# P1_1.net
KiCad netlist of a schematic drawn in EasyEDA Pro
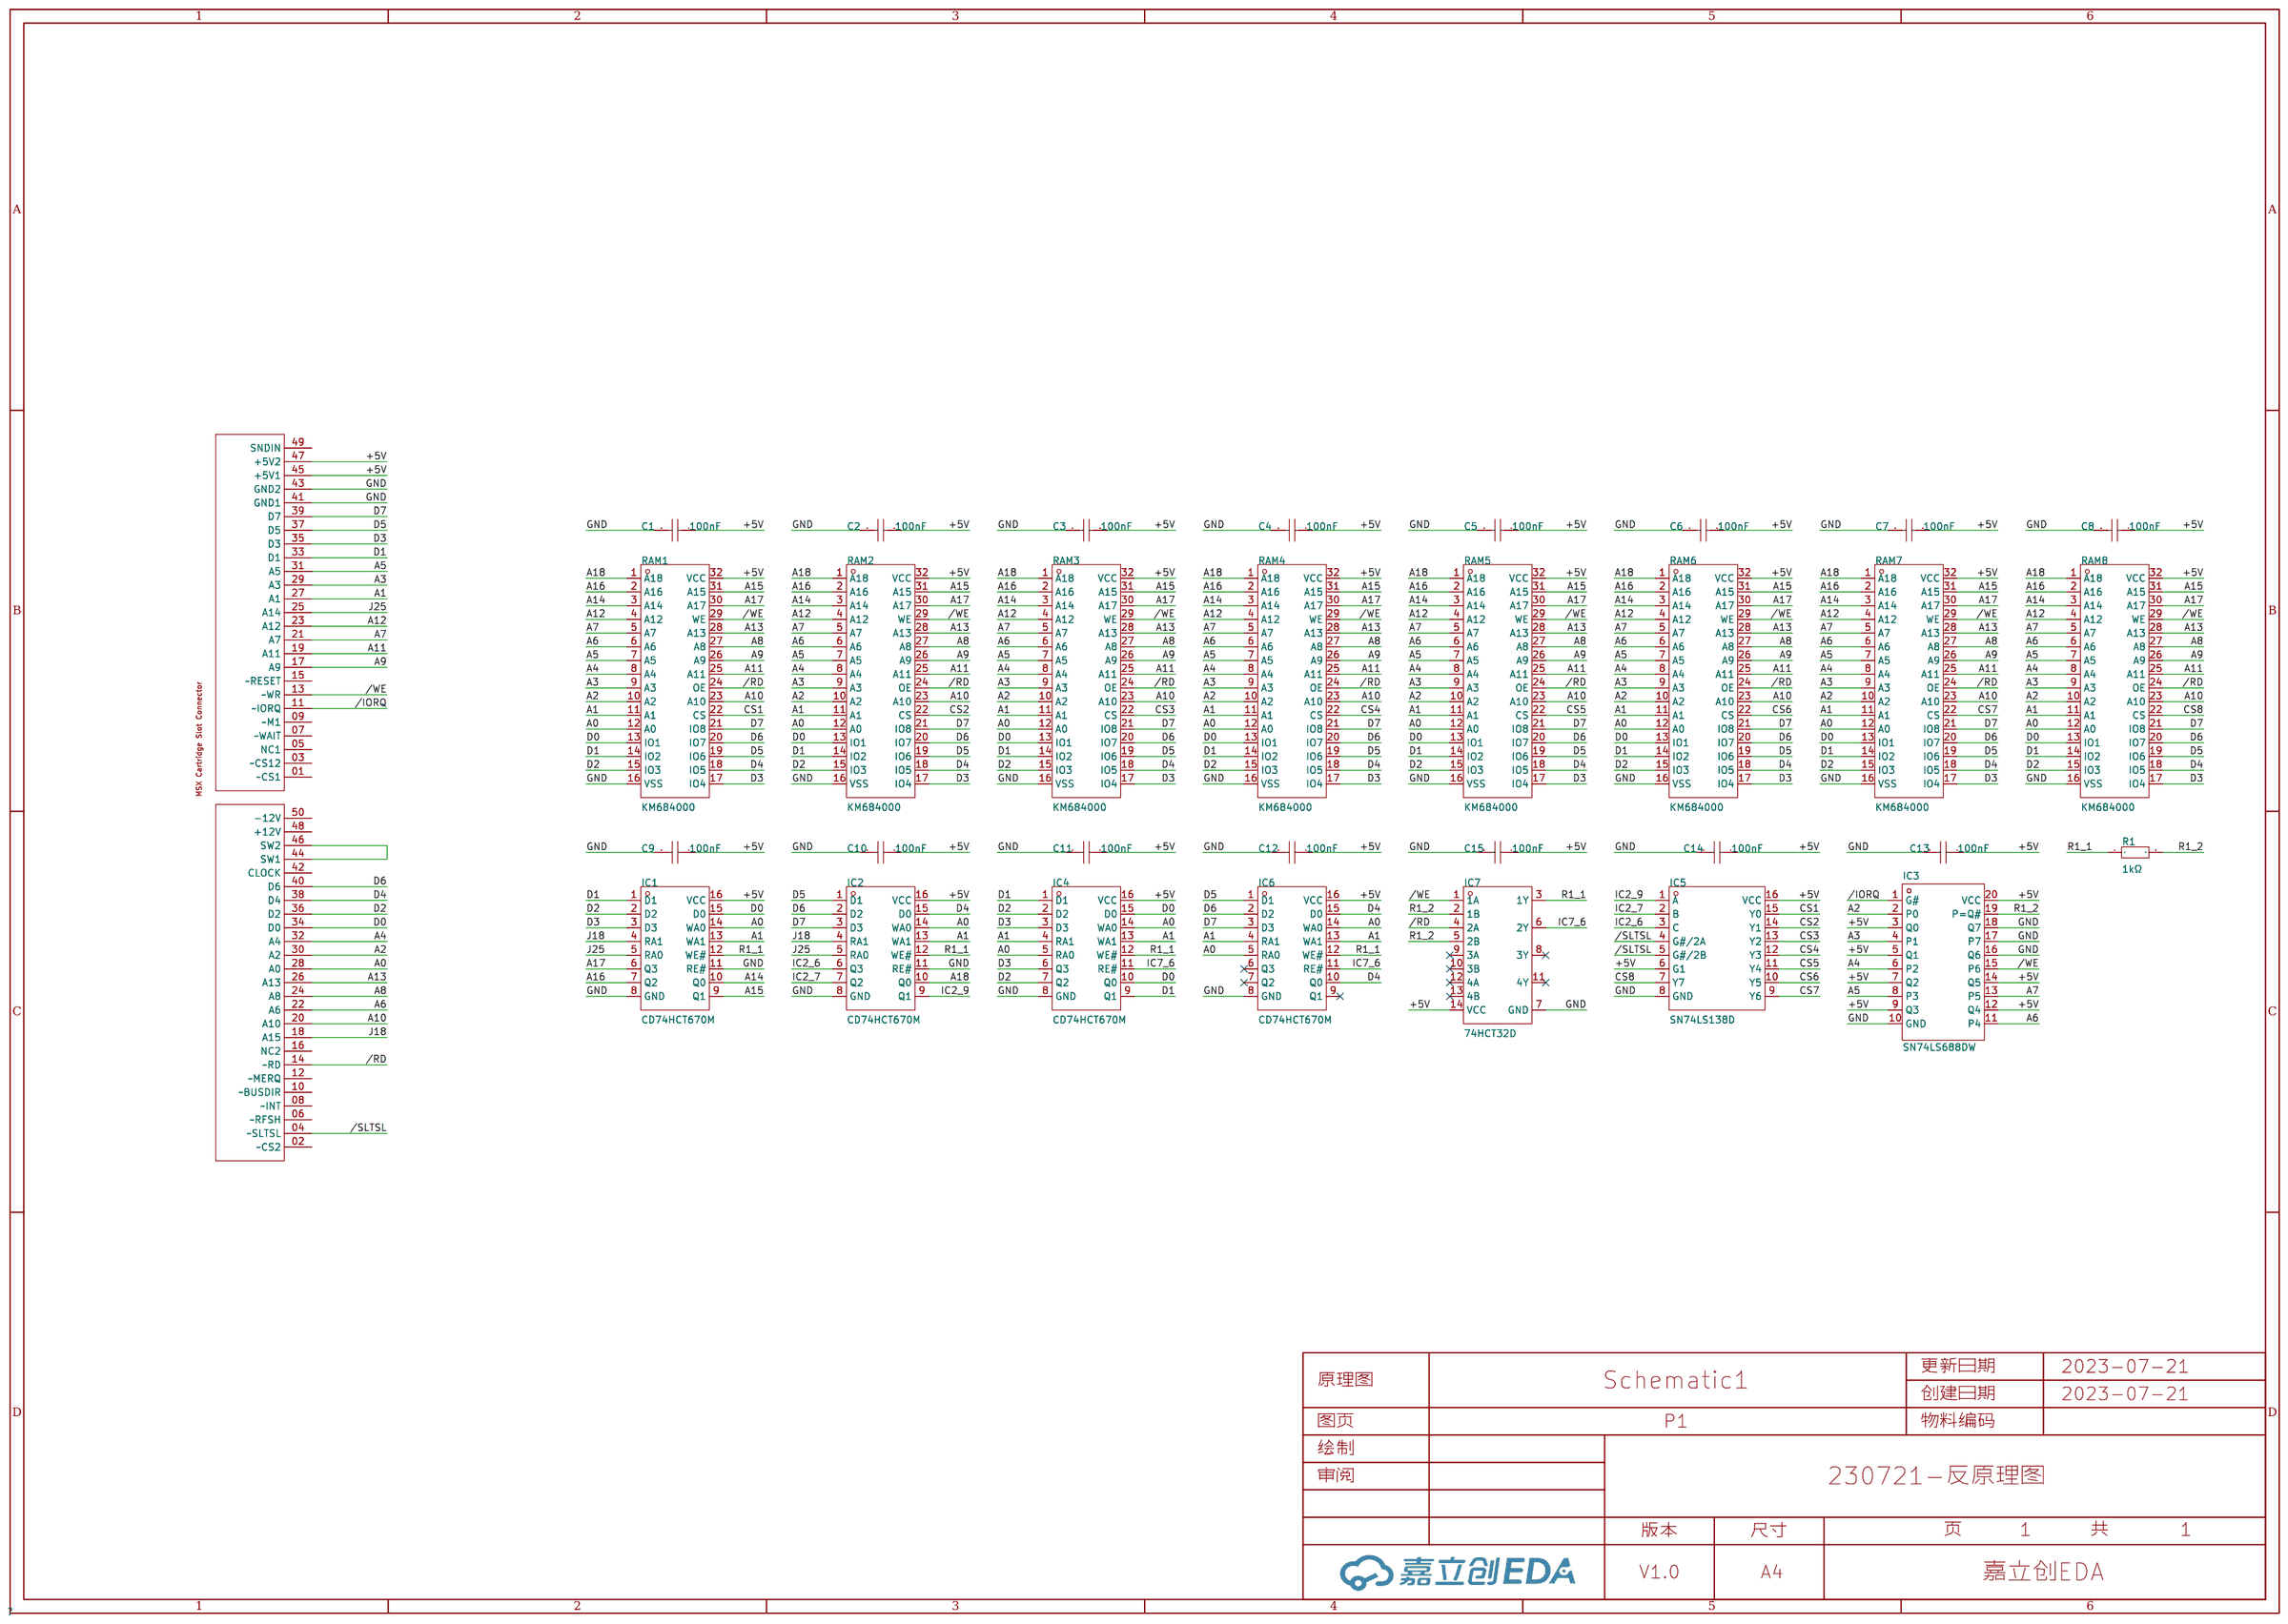
[diagram p0: schematic sheet]

(export (version "E")
  (design (tool "Eeschema 10.0.6"))
  (components
    (comp (ref "C1")
      (value "100nF")
      (footprint "easyedapro:C0805")
      (description "容值:100nF;精度:±10%;额定电压:50V;材质(温度系数):X7R;")
      (fields
        (field (name "Manufacturer Part") "CC0805KRX7R9BB104")
        (field (name "Manufacturer") "YAGEO(国巨)")
      )
      (libsource (lib "easyedapro") (part "CC0805KRX7R9BB104"))
    )
    (comp (ref "C2")
      (value "100nF")
      (footprint "easyedapro:C0805")
      (description "容值:100nF;精度:±10%;额定电压:50V;材质(温度系数):X7R;")
      (fields
        (field (name "Manufacturer Part") "CC0805KRX7R9BB104")
        (field (name "Manufacturer") "YAGEO(国巨)")
      )
      (libsource (lib "easyedapro") (part "CC0805KRX7R9BB104"))
    )
    (comp (ref "C3")
      (value "100nF")
      (footprint "easyedapro:C0805")
      (description "容值:100nF;精度:±10%;额定电压:50V;材质(温度系数):X7R;")
      (fields
        (field (name "Manufacturer Part") "CC0805KRX7R9BB104")
        (field (name "Manufacturer") "YAGEO(国巨)")
      )
      (libsource (lib "easyedapro") (part "CC0805KRX7R9BB104"))
    )
    (comp (ref "C4")
      (value "100nF")
      (footprint "easyedapro:C0805")
      (description "容值:100nF;精度:±10%;额定电压:50V;材质(温度系数):X7R;")
      (fields
        (field (name "Manufacturer Part") "CC0805KRX7R9BB104")
        (field (name "Manufacturer") "YAGEO(国巨)")
      )
      (libsource (lib "easyedapro") (part "CC0805KRX7R9BB104"))
    )
    (comp (ref "C5")
      (value "100nF")
      (footprint "easyedapro:C0805")
      (description "容值:100nF;精度:±10%;额定电压:50V;材质(温度系数):X7R;")
      (fields
        (field (name "Manufacturer Part") "CC0805KRX7R9BB104")
        (field (name "Manufacturer") "YAGEO(国巨)")
      )
      (libsource (lib "easyedapro") (part "CC0805KRX7R9BB104"))
    )
    (comp (ref "C6")
      (value "100nF")
      (footprint "easyedapro:C0805")
      (description "容值:100nF;精度:±10%;额定电压:50V;材质(温度系数):X7R;")
      (fields
        (field (name "Manufacturer Part") "CC0805KRX7R9BB104")
        (field (name "Manufacturer") "YAGEO(国巨)")
      )
      (libsource (lib "easyedapro") (part "CC0805KRX7R9BB104"))
    )
    (comp (ref "C7")
      (value "100nF")
      (footprint "easyedapro:C0805")
      (description "容值:100nF;精度:±10%;额定电压:50V;材质(温度系数):X7R;")
      (fields
        (field (name "Manufacturer Part") "CC0805KRX7R9BB104")
        (field (name "Manufacturer") "YAGEO(国巨)")
      )
      (libsource (lib "easyedapro") (part "CC0805KRX7R9BB104"))
    )
    (comp (ref "C8")
      (value "100nF")
      (footprint "easyedapro:C0805")
      (description "容值:100nF;精度:±10%;额定电压:50V;材质(温度系数):X7R;")
      (fields
        (field (name "Manufacturer Part") "CC0805KRX7R9BB104")
        (field (name "Manufacturer") "YAGEO(国巨)")
      )
      (libsource (lib "easyedapro") (part "CC0805KRX7R9BB104"))
    )
    (comp (ref "C9")
      (value "100nF")
      (footprint "easyedapro:C0805")
      (description "容值:100nF;精度:±10%;额定电压:50V;材质(温度系数):X7R;")
      (fields
        (field (name "Manufacturer Part") "CC0805KRX7R9BB104")
        (field (name "Manufacturer") "YAGEO(国巨)")
      )
      (libsource (lib "easyedapro") (part "CC0805KRX7R9BB104"))
    )
    (comp (ref "C10")
      (value "100nF")
      (footprint "easyedapro:C0805")
      (description "容值:100nF;精度:±10%;额定电压:50V;材质(温度系数):X7R;")
      (fields
        (field (name "Manufacturer Part") "CC0805KRX7R9BB104")
        (field (name "Manufacturer") "YAGEO(国巨)")
      )
      (libsource (lib "easyedapro") (part "CC0805KRX7R9BB104"))
    )
    (comp (ref "C11")
      (value "100nF")
      (footprint "easyedapro:C0805")
      (description "容值:100nF;精度:±10%;额定电压:50V;材质(温度系数):X7R;")
      (fields
        (field (name "Manufacturer Part") "CC0805KRX7R9BB104")
        (field (name "Manufacturer") "YAGEO(国巨)")
      )
      (libsource (lib "easyedapro") (part "CC0805KRX7R9BB104"))
    )
    (comp (ref "C12")
      (value "100nF")
      (footprint "easyedapro:C0805")
      (description "容值:100nF;精度:±10%;额定电压:50V;材质(温度系数):X7R;")
      (fields
        (field (name "Manufacturer Part") "CC0805KRX7R9BB104")
        (field (name "Manufacturer") "YAGEO(国巨)")
      )
      (libsource (lib "easyedapro") (part "CC0805KRX7R9BB104"))
    )
    (comp (ref "C13")
      (value "100nF")
      (footprint "easyedapro:C0805")
      (description "容值:100nF;精度:±10%;额定电压:50V;材质(温度系数):X7R;")
      (fields
        (field (name "Manufacturer Part") "CC0805KRX7R9BB104")
        (field (name "Manufacturer") "YAGEO(国巨)")
      )
      (libsource (lib "easyedapro") (part "CC0805KRX7R9BB104"))
    )
    (comp (ref "C14")
      (value "100nF")
      (footprint "easyedapro:C0805")
      (description "容值:100nF;精度:±10%;额定电压:50V;材质(温度系数):X7R;")
      (fields
        (field (name "Manufacturer Part") "CC0805KRX7R9BB104")
        (field (name "Manufacturer") "YAGEO(国巨)")
      )
      (libsource (lib "easyedapro") (part "CC0805KRX7R9BB104"))
    )
    (comp (ref "C15")
      (value "100nF")
      (footprint "easyedapro:C0805")
      (description "容值:100nF;精度:±10%;额定电压:50V;材质(温度系数):X7R;")
      (fields
        (field (name "Manufacturer Part") "CC0805KRX7R9BB104")
        (field (name "Manufacturer") "YAGEO(国巨)")
      )
      (libsource (lib "easyedapro") (part "CC0805KRX7R9BB104"))
    )
    (comp (ref "IC1")
      (value "CD74HCT670M")
      (footprint "easyedapro:SOIC-16_L9.9-W3.9-P1.27-LS6.0-BL")
      (description "高速 CMOS 逻辑 4 x 4 寄存器文件 16-SOIC -55 to 125")
      (fields (field (name "Manufacturer") "TI(德州仪器)"))
      (libsource (lib "easyedapro") (part "CD74HCT670M"))
    )
    (comp (ref "IC2")
      (value "CD74HCT670M")
      (footprint "easyedapro:SOIC-16_L9.9-W3.9-P1.27-LS6.0-BL")
      (description "高速 CMOS 逻辑 4 x 4 寄存器文件 16-SOIC -55 to 125")
      (fields (field (name "Manufacturer") "TI(德州仪器)"))
      (libsource (lib "easyedapro") (part "CD74HCT670M"))
    )
    (comp (ref "IC3")
      (value "SN74LS688DW")
      (footprint "easyedapro:SOIC-20_L12.8-W7.5-P1.27-LS10.3-BL")
      (description "具有使能端的 8 位等值/幅度比较器 (P=Q) 20-SOIC 0 to 70")
      (fields (field (name "Manufacturer") "TI(德州仪器)"))
      (libsource (lib "easyedapro") (part "SN74LS688DW"))
    )
    (comp (ref "IC4")
      (value "CD74HCT670M")
      (footprint "easyedapro:SOIC-16_L9.9-W3.9-P1.27-LS6.0-BL")
      (description "高速 CMOS 逻辑 4 x 4 寄存器文件 16-SOIC -55 to 125")
      (fields (field (name "Manufacturer") "TI(德州仪器)"))
      (libsource (lib "easyedapro") (part "CD74HCT670M"))
    )
    (comp (ref "IC5")
      (value "SN74LS138D")
      (footprint "easyedapro:SOIC-16_L9.9-W3.9-P1.27-LS6.0-BL")
      (description "类型:解码器/多路解器;低电平输出电流(IOL):8mA;高电平输出电流(IOH):400uA;供电电源:单电源;供电电压:4.75V~5.25V;工作温度:0°C~+70°C;")
      (fields (field (name "Manufacturer") "TI(德州仪器)"))
      (libsource (lib "easyedapro") (part "SN74LS138D"))
    )
    (comp (ref "IC6")
      (value "CD74HCT670M")
      (footprint "easyedapro:SOIC-16_L9.9-W3.9-P1.27-LS6.0-BL")
      (description "高速 CMOS 逻辑 4 x 4 寄存器文件 16-SOIC -55 to 125")
      (fields (field (name "Manufacturer") "TI(德州仪器)"))
      (libsource (lib "easyedapro") (part "CD74HCT670M"))
    )
    (comp (ref "IC7")
      (value "74HCT32D")
      (footprint "easyedapro:SOIC-14_L8.6-W3.9-P1.27-LS6.0-BL")
      (description "逻辑类型:或门;通道数:4;电源电压:4.5V~5.5V;静态电流(最大值):1uA;最大传播延迟:18ns@5.5V,50pF;")
      (fields (field (name "Manufacturer") "TOSHIBA(东芝)"))
      (libsource (lib "easyedapro") (part "74HCT32D"))
    )
    (comp (ref "J2")
      (value "MSX_SLOT_CON")
      (libsource (lib "easyedapro") (part "msx2proto-eagle-import_MSX_SLOT_CON"))
    )
    (comp (ref "R1")
      (value "1kΩ")
      (footprint "easyedapro:R0805")
      (description "电阻类型:厚膜电阻;阻值:1kΩ;精度:±1%;功率:125mW;")
      (fields
        (field (name "Manufacturer Part") "0805W8F1001T5E")
        (field (name "Manufacturer") "UNI-ROYAL(厚声)")
      )
      (libsource (lib "easyedapro") (part "0805W8F1001T5E"))
    )
    (comp (ref "RAM1")
      (value "KM684000")
      (footprint "easyedapro:SOP-32_L20.9-W11.4-P1.27-LS14.12-BL")
      (description "存储器类型:-;存储器容量:-;存储器接口类型:-;工作电压:-;")
      (libsource (lib "easyedapro") (part "KM684000"))
    )
    (comp (ref "RAM2")
      (value "KM684000")
      (footprint "easyedapro:SOP-32_L20.9-W11.4-P1.27-LS14.12-BL")
      (description "存储器类型:-;存储器容量:-;存储器接口类型:-;工作电压:-;")
      (libsource (lib "easyedapro") (part "KM684000"))
    )
    (comp (ref "RAM3")
      (value "KM684000")
      (footprint "easyedapro:SOP-32_L20.9-W11.4-P1.27-LS14.12-BL")
      (description "存储器类型:-;存储器容量:-;存储器接口类型:-;工作电压:-;")
      (libsource (lib "easyedapro") (part "KM684000"))
    )
    (comp (ref "RAM4")
      (value "KM684000")
      (footprint "easyedapro:SOP-32_L20.9-W11.4-P1.27-LS14.12-BL")
      (description "存储器类型:-;存储器容量:-;存储器接口类型:-;工作电压:-;")
      (libsource (lib "easyedapro") (part "KM684000"))
    )
    (comp (ref "RAM5")
      (value "KM684000")
      (footprint "easyedapro:SOP-32_L20.9-W11.4-P1.27-LS14.12-BL")
      (description "存储器类型:-;存储器容量:-;存储器接口类型:-;工作电压:-;")
      (libsource (lib "easyedapro") (part "KM684000"))
    )
    (comp (ref "RAM6")
      (value "KM684000")
      (footprint "easyedapro:SOP-32_L20.9-W11.4-P1.27-LS14.12-BL")
      (description "存储器类型:-;存储器容量:-;存储器接口类型:-;工作电压:-;")
      (libsource (lib "easyedapro") (part "KM684000"))
    )
    (comp (ref "RAM7")
      (value "KM684000")
      (footprint "easyedapro:SOP-32_L20.9-W11.4-P1.27-LS14.12-BL")
      (description "存储器类型:-;存储器容量:-;存储器接口类型:-;工作电压:-;")
      (libsource (lib "easyedapro") (part "KM684000"))
    )
    (comp (ref "RAM8")
      (value "KM684000")
      (footprint "easyedapro:SOP-32_L20.9-W11.4-P1.27-LS14.12-BL")
      (description "存储器类型:-;存储器容量:-;存储器接口类型:-;工作电压:-;")
      (libsource (lib "easyedapro") (part "KM684000"))
    )
  )
  (nets
    (net (code "1") (name "/+5V") (class "Default")
      (node (ref "C1") (pin "1") (pinfunction "1_1") (pintype "input"))
      (node (ref "C10") (pin "1") (pinfunction "1_1") (pintype "input"))
      (node (ref "C11") (pin "1") (pinfunction "1_1") (pintype "input"))
      (node (ref "C12") (pin "1") (pinfunction "1_1") (pintype "input"))
      (node (ref "C13") (pin "1") (pinfunction "1_1") (pintype "input"))
      (node (ref "C14") (pin "1") (pinfunction "1_1") (pintype "input"))
      (node (ref "C15") (pin "1") (pinfunction "1_1") (pintype "input"))
      (node (ref "C2") (pin "1") (pinfunction "1_1") (pintype "input"))
      (node (ref "C3") (pin "1") (pinfunction "1_1") (pintype "input"))
      (node (ref "C4") (pin "1") (pinfunction "1_1") (pintype "input"))
      (node (ref "C5") (pin "1") (pinfunction "1_1") (pintype "input"))
      (node (ref "C6") (pin "1") (pinfunction "1_1") (pintype "input"))
      (node (ref "C7") (pin "1") (pinfunction "1_1") (pintype "input"))
      (node (ref "C8") (pin "1") (pinfunction "1_1") (pintype "input"))
      (node (ref "C9") (pin "1") (pinfunction "1_1") (pintype "input"))
      (node (ref "IC1") (pin "16") (pinfunction "VCC_16") (pintype "input"))
      (node (ref "IC2") (pin "16") (pinfunction "VCC_16") (pintype "input"))
      (node (ref "IC3") (pin "12") (pinfunction "Q4_12") (pintype "input"))
      (node (ref "IC3") (pin "14") (pinfunction "Q5_14") (pintype "input"))
      (node (ref "IC3") (pin "20") (pinfunction "VCC_20") (pintype "input"))
      (node (ref "IC3") (pin "3") (pinfunction "Q0_3") (pintype "input"))
      (node (ref "IC3") (pin "5") (pinfunction "Q1_5") (pintype "input"))
      (node (ref "IC3") (pin "7") (pinfunction "Q2_7") (pintype "input"))
      (node (ref "IC3") (pin "9") (pinfunction "Q3_9") (pintype "input"))
      (node (ref "IC4") (pin "16") (pinfunction "VCC_16") (pintype "input"))
      (node (ref "IC5") (pin "16") (pinfunction "VCC_16") (pintype "input"))
      (node (ref "IC5") (pin "6") (pinfunction "G1_6") (pintype "input"))
      (node (ref "IC6") (pin "16") (pinfunction "VCC_16") (pintype "input"))
      (node (ref "IC7") (pin "14") (pinfunction "VCC_14") (pintype "input"))
      (node (ref "J2") (pin "45") (pinfunction "+5V1_45") (pintype "input"))
      (node (ref "J2") (pin "47") (pinfunction "+5V2_47") (pintype "input"))
      (node (ref "RAM1") (pin "32") (pinfunction "VCC_32") (pintype "input"))
      (node (ref "RAM2") (pin "32") (pinfunction "VCC_32") (pintype "input"))
      (node (ref "RAM3") (pin "32") (pinfunction "VCC_32") (pintype "input"))
      (node (ref "RAM4") (pin "32") (pinfunction "VCC_32") (pintype "input"))
      (node (ref "RAM5") (pin "32") (pinfunction "VCC_32") (pintype "input"))
      (node (ref "RAM6") (pin "32") (pinfunction "VCC_32") (pintype "input"))
      (node (ref "RAM7") (pin "32") (pinfunction "VCC_32") (pintype "input"))
      (node (ref "RAM8") (pin "32") (pinfunction "VCC_32") (pintype "input"))
    )
    (net (code "2") (name "/A0") (class "Default")
      (node (ref "IC1") (pin "14") (pinfunction "WA0_14") (pintype "input"))
      (node (ref "IC2") (pin "14") (pinfunction "WA0_14") (pintype "input"))
      (node (ref "IC4") (pin "14") (pinfunction "WA0_14") (pintype "input"))
      (node (ref "IC4") (pin "5") (pinfunction "RA0_5") (pintype "input"))
      (node (ref "IC6") (pin "14") (pinfunction "WA0_14") (pintype "input"))
      (node (ref "IC6") (pin "5") (pinfunction "RA0_5") (pintype "input"))
      (node (ref "J2") (pin "28") (pinfunction "A0_28") (pintype "output"))
      (node (ref "RAM1") (pin "12") (pinfunction "A0_12") (pintype "input"))
      (node (ref "RAM2") (pin "12") (pinfunction "A0_12") (pintype "input"))
      (node (ref "RAM3") (pin "12") (pinfunction "A0_12") (pintype "input"))
      (node (ref "RAM4") (pin "12") (pinfunction "A0_12") (pintype "input"))
      (node (ref "RAM5") (pin "12") (pinfunction "A0_12") (pintype "input"))
      (node (ref "RAM6") (pin "12") (pinfunction "A0_12") (pintype "input"))
      (node (ref "RAM7") (pin "12") (pinfunction "A0_12") (pintype "input"))
      (node (ref "RAM8") (pin "12") (pinfunction "A0_12") (pintype "input"))
    )
    (net (code "3") (name "/A1") (class "Default")
      (node (ref "IC1") (pin "13") (pinfunction "WA1_13") (pintype "input"))
      (node (ref "IC2") (pin "13") (pinfunction "WA1_13") (pintype "input"))
      (node (ref "IC4") (pin "13") (pinfunction "WA1_13") (pintype "input"))
      (node (ref "IC4") (pin "4") (pinfunction "RA1_4") (pintype "input"))
      (node (ref "IC6") (pin "13") (pinfunction "WA1_13") (pintype "input"))
      (node (ref "IC6") (pin "4") (pinfunction "RA1_4") (pintype "input"))
      (node (ref "J2") (pin "27") (pinfunction "A1_27") (pintype "output"))
      (node (ref "RAM1") (pin "11") (pinfunction "A1_11") (pintype "input"))
      (node (ref "RAM2") (pin "11") (pinfunction "A1_11") (pintype "input"))
      (node (ref "RAM3") (pin "11") (pinfunction "A1_11") (pintype "input"))
      (node (ref "RAM4") (pin "11") (pinfunction "A1_11") (pintype "input"))
      (node (ref "RAM5") (pin "11") (pinfunction "A1_11") (pintype "input"))
      (node (ref "RAM6") (pin "11") (pinfunction "A1_11") (pintype "input"))
      (node (ref "RAM7") (pin "11") (pinfunction "A1_11") (pintype "input"))
      (node (ref "RAM8") (pin "11") (pinfunction "A1_11") (pintype "input"))
    )
    (net (code "4") (name "/A2") (class "Default")
      (node (ref "IC3") (pin "2") (pinfunction "P0_2") (pintype "input"))
      (node (ref "J2") (pin "30") (pinfunction "A2_30") (pintype "output"))
      (node (ref "RAM1") (pin "10") (pinfunction "A2_10") (pintype "input"))
      (node (ref "RAM2") (pin "10") (pinfunction "A2_10") (pintype "input"))
      (node (ref "RAM3") (pin "10") (pinfunction "A2_10") (pintype "input"))
      (node (ref "RAM4") (pin "10") (pinfunction "A2_10") (pintype "input"))
      (node (ref "RAM5") (pin "10") (pinfunction "A2_10") (pintype "input"))
      (node (ref "RAM6") (pin "10") (pinfunction "A2_10") (pintype "input"))
      (node (ref "RAM7") (pin "10") (pinfunction "A2_10") (pintype "input"))
      (node (ref "RAM8") (pin "10") (pinfunction "A2_10") (pintype "input"))
    )
    (net (code "5") (name "/A3") (class "Default")
      (node (ref "IC3") (pin "4") (pinfunction "P1_4") (pintype "input"))
      (node (ref "J2") (pin "29") (pinfunction "A3_29") (pintype "output"))
      (node (ref "RAM1") (pin "9") (pinfunction "A3_9") (pintype "input"))
      (node (ref "RAM2") (pin "9") (pinfunction "A3_9") (pintype "input"))
      (node (ref "RAM3") (pin "9") (pinfunction "A3_9") (pintype "input"))
      (node (ref "RAM4") (pin "9") (pinfunction "A3_9") (pintype "input"))
      (node (ref "RAM5") (pin "9") (pinfunction "A3_9") (pintype "input"))
      (node (ref "RAM6") (pin "9") (pinfunction "A3_9") (pintype "input"))
      (node (ref "RAM7") (pin "9") (pinfunction "A3_9") (pintype "input"))
      (node (ref "RAM8") (pin "9") (pinfunction "A3_9") (pintype "input"))
    )
    (net (code "6") (name "/A4") (class "Default")
      (node (ref "IC3") (pin "6") (pinfunction "P2_6") (pintype "input"))
      (node (ref "J2") (pin "32") (pinfunction "A4_32") (pintype "output"))
      (node (ref "RAM1") (pin "8") (pinfunction "A4_8") (pintype "input"))
      (node (ref "RAM2") (pin "8") (pinfunction "A4_8") (pintype "input"))
      (node (ref "RAM3") (pin "8") (pinfunction "A4_8") (pintype "input"))
      (node (ref "RAM4") (pin "8") (pinfunction "A4_8") (pintype "input"))
      (node (ref "RAM5") (pin "8") (pinfunction "A4_8") (pintype "input"))
      (node (ref "RAM6") (pin "8") (pinfunction "A4_8") (pintype "input"))
      (node (ref "RAM7") (pin "8") (pinfunction "A4_8") (pintype "input"))
      (node (ref "RAM8") (pin "8") (pinfunction "A4_8") (pintype "input"))
    )
    (net (code "7") (name "/A5") (class "Default")
      (node (ref "IC3") (pin "8") (pinfunction "P3_8") (pintype "input"))
      (node (ref "J2") (pin "31") (pinfunction "A5_31") (pintype "output"))
      (node (ref "RAM1") (pin "7") (pinfunction "A5_7") (pintype "input"))
      (node (ref "RAM2") (pin "7") (pinfunction "A5_7") (pintype "input"))
      (node (ref "RAM3") (pin "7") (pinfunction "A5_7") (pintype "input"))
      (node (ref "RAM4") (pin "7") (pinfunction "A5_7") (pintype "input"))
      (node (ref "RAM5") (pin "7") (pinfunction "A5_7") (pintype "input"))
      (node (ref "RAM6") (pin "7") (pinfunction "A5_7") (pintype "input"))
      (node (ref "RAM7") (pin "7") (pinfunction "A5_7") (pintype "input"))
      (node (ref "RAM8") (pin "7") (pinfunction "A5_7") (pintype "input"))
    )
    (net (code "8") (name "/A6") (class "Default")
      (node (ref "IC3") (pin "11") (pinfunction "P4_11") (pintype "input"))
      (node (ref "J2") (pin "22") (pinfunction "A6_22") (pintype "output"))
      (node (ref "RAM1") (pin "6") (pinfunction "A6_6") (pintype "input"))
      (node (ref "RAM2") (pin "6") (pinfunction "A6_6") (pintype "input"))
      (node (ref "RAM3") (pin "6") (pinfunction "A6_6") (pintype "input"))
      (node (ref "RAM4") (pin "6") (pinfunction "A6_6") (pintype "input"))
      (node (ref "RAM5") (pin "6") (pinfunction "A6_6") (pintype "input"))
      (node (ref "RAM6") (pin "6") (pinfunction "A6_6") (pintype "input"))
      (node (ref "RAM7") (pin "6") (pinfunction "A6_6") (pintype "input"))
      (node (ref "RAM8") (pin "6") (pinfunction "A6_6") (pintype "input"))
    )
    (net (code "9") (name "/A7") (class "Default")
      (node (ref "IC3") (pin "13") (pinfunction "P5_13") (pintype "input"))
      (node (ref "J2") (pin "21") (pinfunction "A7_21") (pintype "output"))
      (node (ref "RAM1") (pin "5") (pinfunction "A7_5") (pintype "input"))
      (node (ref "RAM2") (pin "5") (pinfunction "A7_5") (pintype "input"))
      (node (ref "RAM3") (pin "5") (pinfunction "A7_5") (pintype "input"))
      (node (ref "RAM4") (pin "5") (pinfunction "A7_5") (pintype "input"))
      (node (ref "RAM5") (pin "5") (pinfunction "A7_5") (pintype "input"))
      (node (ref "RAM6") (pin "5") (pinfunction "A7_5") (pintype "input"))
      (node (ref "RAM7") (pin "5") (pinfunction "A7_5") (pintype "input"))
      (node (ref "RAM8") (pin "5") (pinfunction "A7_5") (pintype "input"))
    )
    (net (code "10") (name "/A8") (class "Default")
      (node (ref "J2") (pin "24") (pinfunction "A8_24") (pintype "output"))
      (node (ref "RAM1") (pin "27") (pinfunction "A8_27") (pintype "input"))
      (node (ref "RAM2") (pin "27") (pinfunction "A8_27") (pintype "input"))
      (node (ref "RAM3") (pin "27") (pinfunction "A8_27") (pintype "input"))
      (node (ref "RAM4") (pin "27") (pinfunction "A8_27") (pintype "input"))
      (node (ref "RAM5") (pin "27") (pinfunction "A8_27") (pintype "input"))
      (node (ref "RAM6") (pin "27") (pinfunction "A8_27") (pintype "input"))
      (node (ref "RAM7") (pin "27") (pinfunction "A8_27") (pintype "input"))
      (node (ref "RAM8") (pin "27") (pinfunction "A8_27") (pintype "input"))
    )
    (net (code "11") (name "/A9") (class "Default")
      (node (ref "J2") (pin "17") (pinfunction "A9_17") (pintype "output"))
      (node (ref "RAM1") (pin "26") (pinfunction "A9_26") (pintype "input"))
      (node (ref "RAM2") (pin "26") (pinfunction "A9_26") (pintype "input"))
      (node (ref "RAM3") (pin "26") (pinfunction "A9_26") (pintype "input"))
      (node (ref "RAM4") (pin "26") (pinfunction "A9_26") (pintype "input"))
      (node (ref "RAM5") (pin "26") (pinfunction "A9_26") (pintype "input"))
      (node (ref "RAM6") (pin "26") (pinfunction "A9_26") (pintype "input"))
      (node (ref "RAM7") (pin "26") (pinfunction "A9_26") (pintype "input"))
      (node (ref "RAM8") (pin "26") (pinfunction "A9_26") (pintype "input"))
    )
    (net (code "12") (name "/A10") (class "Default")
      (node (ref "J2") (pin "20") (pinfunction "A10_20") (pintype "output"))
      (node (ref "RAM1") (pin "23") (pinfunction "A10_23") (pintype "input"))
      (node (ref "RAM2") (pin "23") (pinfunction "A10_23") (pintype "input"))
      (node (ref "RAM3") (pin "23") (pinfunction "A10_23") (pintype "input"))
      (node (ref "RAM4") (pin "23") (pinfunction "A10_23") (pintype "input"))
      (node (ref "RAM5") (pin "23") (pinfunction "A10_23") (pintype "input"))
      (node (ref "RAM6") (pin "23") (pinfunction "A10_23") (pintype "input"))
      (node (ref "RAM7") (pin "23") (pinfunction "A10_23") (pintype "input"))
      (node (ref "RAM8") (pin "23") (pinfunction "A10_23") (pintype "input"))
    )
    (net (code "13") (name "/A11") (class "Default")
      (node (ref "J2") (pin "19") (pinfunction "A11_19") (pintype "output"))
      (node (ref "RAM1") (pin "25") (pinfunction "A11_25") (pintype "input"))
      (node (ref "RAM2") (pin "25") (pinfunction "A11_25") (pintype "input"))
      (node (ref "RAM3") (pin "25") (pinfunction "A11_25") (pintype "input"))
      (node (ref "RAM4") (pin "25") (pinfunction "A11_25") (pintype "input"))
      (node (ref "RAM5") (pin "25") (pinfunction "A11_25") (pintype "input"))
      (node (ref "RAM6") (pin "25") (pinfunction "A11_25") (pintype "input"))
      (node (ref "RAM7") (pin "25") (pinfunction "A11_25") (pintype "input"))
      (node (ref "RAM8") (pin "25") (pinfunction "A11_25") (pintype "input"))
    )
    (net (code "14") (name "/A12") (class "Default")
      (node (ref "J2") (pin "23") (pinfunction "A12_23") (pintype "output"))
      (node (ref "RAM1") (pin "4") (pinfunction "A12_4") (pintype "input"))
      (node (ref "RAM2") (pin "4") (pinfunction "A12_4") (pintype "input"))
      (node (ref "RAM3") (pin "4") (pinfunction "A12_4") (pintype "input"))
      (node (ref "RAM4") (pin "4") (pinfunction "A12_4") (pintype "input"))
      (node (ref "RAM5") (pin "4") (pinfunction "A12_4") (pintype "input"))
      (node (ref "RAM6") (pin "4") (pinfunction "A12_4") (pintype "input"))
      (node (ref "RAM7") (pin "4") (pinfunction "A12_4") (pintype "input"))
      (node (ref "RAM8") (pin "4") (pinfunction "A12_4") (pintype "input"))
    )
    (net (code "15") (name "/A13") (class "Default")
      (node (ref "J2") (pin "26") (pinfunction "A13_26") (pintype "output"))
      (node (ref "RAM1") (pin "28") (pinfunction "A13_28") (pintype "input"))
      (node (ref "RAM2") (pin "28") (pinfunction "A13_28") (pintype "input"))
      (node (ref "RAM3") (pin "28") (pinfunction "A13_28") (pintype "input"))
      (node (ref "RAM4") (pin "28") (pinfunction "A13_28") (pintype "input"))
      (node (ref "RAM5") (pin "28") (pinfunction "A13_28") (pintype "input"))
      (node (ref "RAM6") (pin "28") (pinfunction "A13_28") (pintype "input"))
      (node (ref "RAM7") (pin "28") (pinfunction "A13_28") (pintype "input"))
      (node (ref "RAM8") (pin "28") (pinfunction "A13_28") (pintype "input"))
    )
    (net (code "16") (name "/A14") (class "Default")
      (node (ref "IC1") (pin "10") (pinfunction "Q0_10") (pintype "input"))
      (node (ref "RAM1") (pin "3") (pinfunction "A14_3") (pintype "input"))
      (node (ref "RAM2") (pin "3") (pinfunction "A14_3") (pintype "input"))
      (node (ref "RAM3") (pin "3") (pinfunction "A14_3") (pintype "input"))
      (node (ref "RAM4") (pin "3") (pinfunction "A14_3") (pintype "input"))
      (node (ref "RAM5") (pin "3") (pinfunction "A14_3") (pintype "input"))
      (node (ref "RAM6") (pin "3") (pinfunction "A14_3") (pintype "input"))
      (node (ref "RAM7") (pin "3") (pinfunction "A14_3") (pintype "input"))
      (node (ref "RAM8") (pin "3") (pinfunction "A14_3") (pintype "input"))
    )
    (net (code "17") (name "/A15") (class "Default")
      (node (ref "IC1") (pin "9") (pinfunction "Q1_9") (pintype "input"))
      (node (ref "RAM1") (pin "31") (pinfunction "A15_31") (pintype "input"))
      (node (ref "RAM2") (pin "31") (pinfunction "A15_31") (pintype "input"))
      (node (ref "RAM3") (pin "31") (pinfunction "A15_31") (pintype "input"))
      (node (ref "RAM4") (pin "31") (pinfunction "A15_31") (pintype "input"))
      (node (ref "RAM5") (pin "31") (pinfunction "A15_31") (pintype "input"))
      (node (ref "RAM6") (pin "31") (pinfunction "A15_31") (pintype "input"))
      (node (ref "RAM7") (pin "31") (pinfunction "A15_31") (pintype "input"))
      (node (ref "RAM8") (pin "31") (pinfunction "A15_31") (pintype "input"))
    )
    (net (code "18") (name "/A16") (class "Default")
      (node (ref "IC1") (pin "7") (pinfunction "Q2_7") (pintype "input"))
      (node (ref "RAM1") (pin "2") (pinfunction "A16_2") (pintype "input"))
      (node (ref "RAM2") (pin "2") (pinfunction "A16_2") (pintype "input"))
      (node (ref "RAM3") (pin "2") (pinfunction "A16_2") (pintype "input"))
      (node (ref "RAM4") (pin "2") (pinfunction "A16_2") (pintype "input"))
      (node (ref "RAM5") (pin "2") (pinfunction "A16_2") (pintype "input"))
      (node (ref "RAM6") (pin "2") (pinfunction "A16_2") (pintype "input"))
      (node (ref "RAM7") (pin "2") (pinfunction "A16_2") (pintype "input"))
      (node (ref "RAM8") (pin "2") (pinfunction "A16_2") (pintype "input"))
    )
    (net (code "19") (name "/A17") (class "Default")
      (node (ref "IC1") (pin "6") (pinfunction "Q3_6") (pintype "input"))
      (node (ref "RAM1") (pin "30") (pinfunction "A17_30") (pintype "input"))
      (node (ref "RAM2") (pin "30") (pinfunction "A17_30") (pintype "input"))
      (node (ref "RAM3") (pin "30") (pinfunction "A17_30") (pintype "input"))
      (node (ref "RAM4") (pin "30") (pinfunction "A17_30") (pintype "input"))
      (node (ref "RAM5") (pin "30") (pinfunction "A17_30") (pintype "input"))
      (node (ref "RAM6") (pin "30") (pinfunction "A17_30") (pintype "input"))
      (node (ref "RAM7") (pin "30") (pinfunction "A17_30") (pintype "input"))
      (node (ref "RAM8") (pin "30") (pinfunction "A17_30") (pintype "input"))
    )
    (net (code "20") (name "/A18") (class "Default")
      (node (ref "IC2") (pin "10") (pinfunction "Q0_10") (pintype "input"))
      (node (ref "RAM1") (pin "1") (pinfunction "A18_1") (pintype "input"))
      (node (ref "RAM2") (pin "1") (pinfunction "A18_1") (pintype "input"))
      (node (ref "RAM3") (pin "1") (pinfunction "A18_1") (pintype "input"))
      (node (ref "RAM4") (pin "1") (pinfunction "A18_1") (pintype "input"))
      (node (ref "RAM5") (pin "1") (pinfunction "A18_1") (pintype "input"))
      (node (ref "RAM6") (pin "1") (pinfunction "A18_1") (pintype "input"))
      (node (ref "RAM7") (pin "1") (pinfunction "A18_1") (pintype "input"))
      (node (ref "RAM8") (pin "1") (pinfunction "A18_1") (pintype "input"))
    )
    (net (code "21") (name "/CS1") (class "Default")
      (node (ref "IC5") (pin "15") (pinfunction "Y0_15") (pintype "input"))
      (node (ref "RAM1") (pin "22") (pinfunction "CS_22") (pintype "input"))
    )
    (net (code "22") (name "/CS2") (class "Default")
      (node (ref "IC5") (pin "14") (pinfunction "Y1_14") (pintype "input"))
      (node (ref "RAM2") (pin "22") (pinfunction "CS_22") (pintype "input"))
    )
    (net (code "23") (name "/CS3") (class "Default")
      (node (ref "IC5") (pin "13") (pinfunction "Y2_13") (pintype "input"))
      (node (ref "RAM3") (pin "22") (pinfunction "CS_22") (pintype "input"))
    )
    (net (code "24") (name "/CS4") (class "Default")
      (node (ref "IC5") (pin "12") (pinfunction "Y3_12") (pintype "input"))
      (node (ref "RAM4") (pin "22") (pinfunction "CS_22") (pintype "input"))
    )
    (net (code "25") (name "/CS5") (class "Default")
      (node (ref "IC5") (pin "11") (pinfunction "Y4_11") (pintype "input"))
      (node (ref "RAM5") (pin "22") (pinfunction "CS_22") (pintype "input"))
    )
    (net (code "26") (name "/CS6") (class "Default")
      (node (ref "IC5") (pin "10") (pinfunction "Y5_10") (pintype "input"))
      (node (ref "RAM6") (pin "22") (pinfunction "CS_22") (pintype "input"))
    )
    (net (code "27") (name "/CS7") (class "Default")
      (node (ref "IC5") (pin "9") (pinfunction "Y6_9") (pintype "input"))
      (node (ref "RAM7") (pin "22") (pinfunction "CS_22") (pintype "input"))
    )
    (net (code "28") (name "/CS8") (class "Default")
      (node (ref "IC5") (pin "7") (pinfunction "Y7_7") (pintype "input"))
      (node (ref "RAM8") (pin "22") (pinfunction "CS_22") (pintype "input"))
    )
    (net (code "29") (name "/D0") (class "Default")
      (node (ref "IC1") (pin "15") (pinfunction "D0_15") (pintype "input"))
      (node (ref "IC4") (pin "10") (pinfunction "Q0_10") (pintype "input"))
      (node (ref "IC4") (pin "15") (pinfunction "D0_15") (pintype "input"))
      (node (ref "J2") (pin "34") (pinfunction "D0_34") (pintype "bidirectional"))
      (node (ref "RAM1") (pin "13") (pinfunction "IO1_13") (pintype "input"))
      (node (ref "RAM2") (pin "13") (pinfunction "IO1_13") (pintype "input"))
      (node (ref "RAM3") (pin "13") (pinfunction "IO1_13") (pintype "input"))
      (node (ref "RAM4") (pin "13") (pinfunction "IO1_13") (pintype "input"))
      (node (ref "RAM5") (pin "13") (pinfunction "IO1_13") (pintype "input"))
      (node (ref "RAM6") (pin "13") (pinfunction "IO1_13") (pintype "input"))
      (node (ref "RAM7") (pin "13") (pinfunction "IO1_13") (pintype "input"))
      (node (ref "RAM8") (pin "13") (pinfunction "IO1_13") (pintype "input"))
    )
    (net (code "30") (name "/D1") (class "Default")
      (node (ref "IC1") (pin "1") (pinfunction "D1_1") (pintype "input"))
      (node (ref "IC4") (pin "1") (pinfunction "D1_1") (pintype "input"))
      (node (ref "IC4") (pin "9") (pinfunction "Q1_9") (pintype "input"))
      (node (ref "J2") (pin "33") (pinfunction "D1_33") (pintype "bidirectional"))
      (node (ref "RAM1") (pin "14") (pinfunction "IO2_14") (pintype "input"))
      (node (ref "RAM2") (pin "14") (pinfunction "IO2_14") (pintype "input"))
      (node (ref "RAM3") (pin "14") (pinfunction "IO2_14") (pintype "input"))
      (node (ref "RAM4") (pin "14") (pinfunction "IO2_14") (pintype "input"))
      (node (ref "RAM5") (pin "14") (pinfunction "IO2_14") (pintype "input"))
      (node (ref "RAM6") (pin "14") (pinfunction "IO2_14") (pintype "input"))
      (node (ref "RAM7") (pin "14") (pinfunction "IO2_14") (pintype "input"))
      (node (ref "RAM8") (pin "14") (pinfunction "IO2_14") (pintype "input"))
    )
    (net (code "31") (name "/D2") (class "Default")
      (node (ref "IC1") (pin "2") (pinfunction "D2_2") (pintype "input"))
      (node (ref "IC4") (pin "2") (pinfunction "D2_2") (pintype "input"))
      (node (ref "IC4") (pin "7") (pinfunction "Q2_7") (pintype "input"))
      (node (ref "J2") (pin "36") (pinfunction "D2_36") (pintype "bidirectional"))
      (node (ref "RAM1") (pin "15") (pinfunction "IO3_15") (pintype "input"))
      (node (ref "RAM2") (pin "15") (pinfunction "IO3_15") (pintype "input"))
      (node (ref "RAM3") (pin "15") (pinfunction "IO3_15") (pintype "input"))
      (node (ref "RAM4") (pin "15") (pinfunction "IO3_15") (pintype "input"))
      (node (ref "RAM5") (pin "15") (pinfunction "IO3_15") (pintype "input"))
      (node (ref "RAM6") (pin "15") (pinfunction "IO3_15") (pintype "input"))
      (node (ref "RAM7") (pin "15") (pinfunction "IO3_15") (pintype "input"))
      (node (ref "RAM8") (pin "15") (pinfunction "IO3_15") (pintype "input"))
    )
    (net (code "32") (name "/D3") (class "Default")
      (node (ref "IC1") (pin "3") (pinfunction "D3_3") (pintype "input"))
      (node (ref "IC4") (pin "3") (pinfunction "D3_3") (pintype "input"))
      (node (ref "IC4") (pin "6") (pinfunction "Q3_6") (pintype "input"))
      (node (ref "J2") (pin "35") (pinfunction "D3_35") (pintype "bidirectional"))
      (node (ref "RAM1") (pin "17") (pinfunction "IO4_17") (pintype "input"))
      (node (ref "RAM2") (pin "17") (pinfunction "IO4_17") (pintype "input"))
      (node (ref "RAM3") (pin "17") (pinfunction "IO4_17") (pintype "input"))
      (node (ref "RAM4") (pin "17") (pinfunction "IO4_17") (pintype "input"))
      (node (ref "RAM5") (pin "17") (pinfunction "IO4_17") (pintype "input"))
      (node (ref "RAM6") (pin "17") (pinfunction "IO4_17") (pintype "input"))
      (node (ref "RAM7") (pin "17") (pinfunction "IO4_17") (pintype "input"))
      (node (ref "RAM8") (pin "17") (pinfunction "IO4_17") (pintype "input"))
    )
    (net (code "33") (name "/D4") (class "Default")
      (node (ref "IC2") (pin "15") (pinfunction "D0_15") (pintype "input"))
      (node (ref "IC6") (pin "10") (pinfunction "Q0_10") (pintype "input"))
      (node (ref "IC6") (pin "15") (pinfunction "D0_15") (pintype "input"))
      (node (ref "J2") (pin "38") (pinfunction "D4_38") (pintype "bidirectional"))
      (node (ref "RAM1") (pin "18") (pinfunction "IO5_18") (pintype "input"))
      (node (ref "RAM2") (pin "18") (pinfunction "IO5_18") (pintype "input"))
      (node (ref "RAM3") (pin "18") (pinfunction "IO5_18") (pintype "input"))
      (node (ref "RAM4") (pin "18") (pinfunction "IO5_18") (pintype "input"))
      (node (ref "RAM5") (pin "18") (pinfunction "IO5_18") (pintype "input"))
      (node (ref "RAM6") (pin "18") (pinfunction "IO5_18") (pintype "input"))
      (node (ref "RAM7") (pin "18") (pinfunction "IO5_18") (pintype "input"))
      (node (ref "RAM8") (pin "18") (pinfunction "IO5_18") (pintype "input"))
    )
    (net (code "34") (name "/D5") (class "Default")
      (node (ref "IC2") (pin "1") (pinfunction "D1_1") (pintype "input"))
      (node (ref "IC6") (pin "1") (pinfunction "D1_1") (pintype "input"))
      (node (ref "J2") (pin "37") (pinfunction "D5_37") (pintype "bidirectional"))
      (node (ref "RAM1") (pin "19") (pinfunction "IO6_19") (pintype "input"))
      (node (ref "RAM2") (pin "19") (pinfunction "IO6_19") (pintype "input"))
      (node (ref "RAM3") (pin "19") (pinfunction "IO6_19") (pintype "input"))
      (node (ref "RAM4") (pin "19") (pinfunction "IO6_19") (pintype "input"))
      (node (ref "RAM5") (pin "19") (pinfunction "IO6_19") (pintype "input"))
      (node (ref "RAM6") (pin "19") (pinfunction "IO6_19") (pintype "input"))
      (node (ref "RAM7") (pin "19") (pinfunction "IO6_19") (pintype "input"))
      (node (ref "RAM8") (pin "19") (pinfunction "IO6_19") (pintype "input"))
    )
    (net (code "35") (name "/D6") (class "Default")
      (node (ref "IC2") (pin "2") (pinfunction "D2_2") (pintype "input"))
      (node (ref "IC6") (pin "2") (pinfunction "D2_2") (pintype "input"))
      (node (ref "J2") (pin "40") (pinfunction "D6_40") (pintype "bidirectional"))
      (node (ref "RAM1") (pin "20") (pinfunction "IO7_20") (pintype "input"))
      (node (ref "RAM2") (pin "20") (pinfunction "IO7_20") (pintype "input"))
      (node (ref "RAM3") (pin "20") (pinfunction "IO7_20") (pintype "input"))
      (node (ref "RAM4") (pin "20") (pinfunction "IO7_20") (pintype "input"))
      (node (ref "RAM5") (pin "20") (pinfunction "IO7_20") (pintype "input"))
      (node (ref "RAM6") (pin "20") (pinfunction "IO7_20") (pintype "input"))
      (node (ref "RAM7") (pin "20") (pinfunction "IO7_20") (pintype "input"))
      (node (ref "RAM8") (pin "20") (pinfunction "IO7_20") (pintype "input"))
    )
    (net (code "36") (name "/D7") (class "Default")
      (node (ref "IC2") (pin "3") (pinfunction "D3_3") (pintype "input"))
      (node (ref "IC6") (pin "3") (pinfunction "D3_3") (pintype "input"))
      (node (ref "J2") (pin "39") (pinfunction "D7_39") (pintype "bidirectional"))
      (node (ref "RAM1") (pin "21") (pinfunction "IO8_21") (pintype "input"))
      (node (ref "RAM2") (pin "21") (pinfunction "IO8_21") (pintype "input"))
      (node (ref "RAM3") (pin "21") (pinfunction "IO8_21") (pintype "input"))
      (node (ref "RAM4") (pin "21") (pinfunction "IO8_21") (pintype "input"))
      (node (ref "RAM5") (pin "21") (pinfunction "IO8_21") (pintype "input"))
      (node (ref "RAM6") (pin "21") (pinfunction "IO8_21") (pintype "input"))
      (node (ref "RAM7") (pin "21") (pinfunction "IO8_21") (pintype "input"))
      (node (ref "RAM8") (pin "21") (pinfunction "IO8_21") (pintype "input"))
    )
    (net (code "37") (name "/GND") (class "Default")
      (node (ref "C1") (pin "2") (pinfunction "2_2") (pintype "input"))
      (node (ref "C10") (pin "2") (pinfunction "2_2") (pintype "input"))
      (node (ref "C11") (pin "2") (pinfunction "2_2") (pintype "input"))
      (node (ref "C12") (pin "2") (pinfunction "2_2") (pintype "input"))
      (node (ref "C13") (pin "2") (pinfunction "2_2") (pintype "input"))
      (node (ref "C14") (pin "2") (pinfunction "2_2") (pintype "input"))
      (node (ref "C15") (pin "2") (pinfunction "2_2") (pintype "input"))
      (node (ref "C2") (pin "2") (pinfunction "2_2") (pintype "input"))
      (node (ref "C3") (pin "2") (pinfunction "2_2") (pintype "input"))
      (node (ref "C4") (pin "2") (pinfunction "2_2") (pintype "input"))
      (node (ref "C5") (pin "2") (pinfunction "2_2") (pintype "input"))
      (node (ref "C6") (pin "2") (pinfunction "2_2") (pintype "input"))
      (node (ref "C7") (pin "2") (pinfunction "2_2") (pintype "input"))
      (node (ref "C8") (pin "2") (pinfunction "2_2") (pintype "input"))
      (node (ref "C9") (pin "2") (pinfunction "2_2") (pintype "input"))
      (node (ref "IC1") (pin "11") (pinfunction "RE#_11") (pintype "input"))
      (node (ref "IC1") (pin "8") (pinfunction "GND_8") (pintype "input"))
      (node (ref "IC2") (pin "11") (pinfunction "RE#_11") (pintype "input"))
      (node (ref "IC2") (pin "8") (pinfunction "GND_8") (pintype "input"))
      (node (ref "IC3") (pin "10") (pinfunction "GND_10") (pintype "input"))
      (node (ref "IC3") (pin "16") (pinfunction "Q6_16") (pintype "input"))
      (node (ref "IC3") (pin "17") (pinfunction "P7_17") (pintype "input"))
      (node (ref "IC3") (pin "18") (pinfunction "Q7_18") (pintype "input"))
      (node (ref "IC4") (pin "8") (pinfunction "GND_8") (pintype "input"))
      (node (ref "IC5") (pin "8") (pinfunction "GND_8") (pintype "input"))
      (node (ref "IC6") (pin "8") (pinfunction "GND_8") (pintype "input"))
      (node (ref "IC7") (pin "7") (pinfunction "GND_7") (pintype "input"))
      (node (ref "J2") (pin "41") (pinfunction "GND1_41") (pintype "input"))
      (node (ref "J2") (pin "43") (pinfunction "GND2_43") (pintype "input"))
      (node (ref "RAM1") (pin "16") (pinfunction "VSS_16") (pintype "input"))
      (node (ref "RAM2") (pin "16") (pinfunction "VSS_16") (pintype "input"))
      (node (ref "RAM3") (pin "16") (pinfunction "VSS_16") (pintype "input"))
      (node (ref "RAM4") (pin "16") (pinfunction "VSS_16") (pintype "input"))
      (node (ref "RAM5") (pin "16") (pinfunction "VSS_16") (pintype "input"))
      (node (ref "RAM6") (pin "16") (pinfunction "VSS_16") (pintype "input"))
      (node (ref "RAM7") (pin "16") (pinfunction "VSS_16") (pintype "input"))
      (node (ref "RAM8") (pin "16") (pinfunction "VSS_16") (pintype "input"))
    )
    (net (code "38") (name "/IC2_6") (class "Default")
      (node (ref "IC2") (pin "6") (pinfunction "Q3_6") (pintype "input"))
      (node (ref "IC5") (pin "3") (pinfunction "C_3") (pintype "input"))
    )
    (net (code "39") (name "/IC2_7") (class "Default")
      (node (ref "IC2") (pin "7") (pinfunction "Q2_7") (pintype "input"))
      (node (ref "IC5") (pin "2") (pinfunction "B_2") (pintype "input"))
    )
    (net (code "40") (name "/IC2_9") (class "Default")
      (node (ref "IC2") (pin "9") (pinfunction "Q1_9") (pintype "input"))
      (node (ref "IC5") (pin "1") (pinfunction "A_1") (pintype "input"))
    )
    (net (code "41") (name "/IC7_6") (class "Default")
      (node (ref "IC4") (pin "11") (pinfunction "RE#_11") (pintype "input"))
      (node (ref "IC6") (pin "11") (pinfunction "RE#_11") (pintype "input"))
      (node (ref "IC7") (pin "6") (pinfunction "2Y_6") (pintype "input"))
    )
    (net (code "42") (name "/J18") (class "Default")
      (node (ref "IC1") (pin "4") (pinfunction "RA1_4") (pintype "input"))
      (node (ref "IC2") (pin "4") (pinfunction "RA1_4") (pintype "input"))
      (node (ref "J2") (pin "18") (pinfunction "A15_18") (pintype "output"))
    )
    (net (code "43") (name "/J25") (class "Default")
      (node (ref "IC1") (pin "5") (pinfunction "RA0_5") (pintype "input"))
      (node (ref "IC2") (pin "5") (pinfunction "RA0_5") (pintype "input"))
      (node (ref "J2") (pin "25") (pinfunction "A14_25") (pintype "output"))
    )
    (net (code "44") (name "/R1_1") (class "Default")
      (node (ref "IC1") (pin "12") (pinfunction "WE#_12") (pintype "input"))
      (node (ref "IC2") (pin "12") (pinfunction "WE#_12") (pintype "input"))
      (node (ref "IC4") (pin "12") (pinfunction "WE#_12") (pintype "input"))
      (node (ref "IC6") (pin "12") (pinfunction "WE#_12") (pintype "input"))
      (node (ref "IC7") (pin "3") (pinfunction "1Y_3") (pintype "input"))
      (node (ref "R1") (pin "1") (pinfunction "1_1") (pintype "input"))
    )
    (net (code "45") (name "/R1_2") (class "Default")
      (node (ref "IC3") (pin "19") (pinfunction "P=Q#_19") (pintype "input"))
      (node (ref "IC7") (pin "2") (pinfunction "1B_2") (pintype "input"))
      (node (ref "IC7") (pin "5") (pinfunction "2B_5") (pintype "input"))
      (node (ref "R1") (pin "2") (pinfunction "2_2") (pintype "input"))
    )
    (net (code "46") (name "/{slash}IORQ") (class "Default")
      (node (ref "IC3") (pin "1") (pinfunction "G#_1") (pintype "input"))
      (node (ref "J2") (pin "11") (pinfunction "~IORQ_11") (pintype "output"))
    )
    (net (code "47") (name "/{slash}RD") (class "Default")
      (node (ref "IC7") (pin "4") (pinfunction "2A_4") (pintype "input"))
      (node (ref "J2") (pin "14") (pinfunction "~RD_14") (pintype "output"))
      (node (ref "RAM1") (pin "24") (pinfunction "OE_24") (pintype "input"))
      (node (ref "RAM2") (pin "24") (pinfunction "OE_24") (pintype "input"))
      (node (ref "RAM3") (pin "24") (pinfunction "OE_24") (pintype "input"))
      (node (ref "RAM4") (pin "24") (pinfunction "OE_24") (pintype "input"))
      (node (ref "RAM5") (pin "24") (pinfunction "OE_24") (pintype "input"))
      (node (ref "RAM6") (pin "24") (pinfunction "OE_24") (pintype "input"))
      (node (ref "RAM7") (pin "24") (pinfunction "OE_24") (pintype "input"))
      (node (ref "RAM8") (pin "24") (pinfunction "OE_24") (pintype "input"))
    )
    (net (code "48") (name "/{slash}SLTSL") (class "Default")
      (node (ref "IC5") (pin "4") (pinfunction "G#/2A_4") (pintype "input"))
      (node (ref "IC5") (pin "5") (pinfunction "G#/2B_5") (pintype "input"))
      (node (ref "J2") (pin "04") (pinfunction "~SLTSL_04") (pintype "output"))
    )
    (net (code "49") (name "/{slash}WE") (class "Default")
      (node (ref "IC3") (pin "15") (pinfunction "P6_15") (pintype "input"))
      (node (ref "IC7") (pin "1") (pinfunction "1A_1") (pintype "input"))
      (node (ref "J2") (pin "13") (pinfunction "~WR_13") (pintype "output"))
      (node (ref "RAM1") (pin "29") (pinfunction "WE_29") (pintype "input"))
      (node (ref "RAM2") (pin "29") (pinfunction "WE_29") (pintype "input"))
      (node (ref "RAM3") (pin "29") (pinfunction "WE_29") (pintype "input"))
      (node (ref "RAM4") (pin "29") (pinfunction "WE_29") (pintype "input"))
      (node (ref "RAM5") (pin "29") (pinfunction "WE_29") (pintype "input"))
      (node (ref "RAM6") (pin "29") (pinfunction "WE_29") (pintype "input"))
      (node (ref "RAM7") (pin "29") (pinfunction "WE_29") (pintype "input"))
      (node (ref "RAM8") (pin "29") (pinfunction "WE_29") (pintype "input"))
    )
    (net (code "50") (name "Net-(J2-SW1)") (class "Default")
      (node (ref "J2") (pin "44") (pinfunction "SW1_44") (pintype "input"))
      (node (ref "J2") (pin "46") (pinfunction "SW2_46") (pintype "input"))
    )
    (net (code "51") (name "unconnected-(IC6-Q1-Pad9)") (class "Default")
      (node (ref "IC6") (pin "9") (pinfunction "Q1_9") (pintype "input+no_connect"))
    )
    (net (code "52") (name "unconnected-(IC6-Q2-Pad7)") (class "Default")
      (node (ref "IC6") (pin "7") (pinfunction "Q2_7") (pintype "input+no_connect"))
    )
    (net (code "53") (name "unconnected-(IC6-Q3-Pad6)") (class "Default")
      (node (ref "IC6") (pin "6") (pinfunction "Q3_6") (pintype "input+no_connect"))
    )
    (net (code "54") (name "unconnected-(IC7-3A-Pad9)") (class "Default")
      (node (ref "IC7") (pin "9") (pinfunction "3A_9") (pintype "input+no_connect"))
    )
    (net (code "55") (name "unconnected-(IC7-3B-Pad10)") (class "Default")
      (node (ref "IC7") (pin "10") (pinfunction "3B_10") (pintype "input+no_connect"))
    )
    (net (code "56") (name "unconnected-(IC7-3Y-Pad8)") (class "Default")
      (node (ref "IC7") (pin "8") (pinfunction "3Y_8") (pintype "input+no_connect"))
    )
    (net (code "57") (name "unconnected-(IC7-4A-Pad12)") (class "Default")
      (node (ref "IC7") (pin "12") (pinfunction "4A_12") (pintype "input+no_connect"))
    )
    (net (code "58") (name "unconnected-(IC7-4B-Pad13)") (class "Default")
      (node (ref "IC7") (pin "13") (pinfunction "4B_13") (pintype "input+no_connect"))
    )
    (net (code "59") (name "unconnected-(IC7-4Y-Pad11)") (class "Default")
      (node (ref "IC7") (pin "11") (pinfunction "4Y_11") (pintype "input+no_connect"))
    )
    (net (code "60") (name "unconnected-(J2-+12V-Pad48)") (class "Default")
      (node (ref "J2") (pin "48") (pinfunction "+12V_48") (pintype "input"))
    )
    (net (code "61") (name "unconnected-(J2--12V-Pad50)") (class "Default")
      (node (ref "J2") (pin "50") (pinfunction "-12V_50") (pintype "input"))
    )
    (net (code "62") (name "unconnected-(J2-CLOCK-Pad42)") (class "Default")
      (node (ref "J2") (pin "42") (pinfunction "CLOCK_42") (pintype "output"))
    )
    (net (code "63") (name "unconnected-(J2-NC1-Pad05)") (class "Default")
      (node (ref "J2") (pin "05") (pinfunction "NC1_05") (pintype "input"))
    )
    (net (code "64") (name "unconnected-(J2-NC2-Pad16)") (class "Default")
      (node (ref "J2") (pin "16") (pinfunction "NC2_16") (pintype "input"))
    )
    (net (code "65") (name "unconnected-(J2-SNDIN-Pad49)") (class "Default")
      (node (ref "J2") (pin "49") (pinfunction "SNDIN_49") (pintype "input"))
    )
    (net (code "66") (name "unconnected-(J2-~BUSDIR-Pad10)") (class "Default")
      (node (ref "J2") (pin "10") (pinfunction "~BUSDIR_10") (pintype "input"))
    )
    (net (code "67") (name "unconnected-(J2-~CS1-Pad01)") (class "Default")
      (node (ref "J2") (pin "01") (pinfunction "~CS1_01") (pintype "output"))
    )
    (net (code "68") (name "unconnected-(J2-~CS2-Pad02)") (class "Default")
      (node (ref "J2") (pin "02") (pinfunction "~CS2_02") (pintype "output"))
    )
    (net (code "69") (name "unconnected-(J2-~CS12-Pad03)") (class "Default")
      (node (ref "J2") (pin "03") (pinfunction "~CS12_03") (pintype "output"))
    )
    (net (code "70") (name "unconnected-(J2-~INT-Pad08)") (class "Default")
      (node (ref "J2") (pin "08") (pinfunction "~INT_08") (pintype "input"))
    )
    (net (code "71") (name "unconnected-(J2-~M1-Pad09)") (class "Default")
      (node (ref "J2") (pin "09") (pinfunction "~M1_09") (pintype "output"))
    )
    (net (code "72") (name "unconnected-(J2-~MERQ-Pad12)") (class "Default")
      (node (ref "J2") (pin "12") (pinfunction "~MERQ_12") (pintype "output"))
    )
    (net (code "73") (name "unconnected-(J2-~RESET-Pad15)") (class "Default")
      (node (ref "J2") (pin "15") (pinfunction "~RESET_15") (pintype "output"))
    )
    (net (code "74") (name "unconnected-(J2-~RFSH-Pad06)") (class "Default")
      (node (ref "J2") (pin "06") (pinfunction "~RFSH_06") (pintype "output"))
    )
    (net (code "75") (name "unconnected-(J2-~WAIT-Pad07)") (class "Default")
      (node (ref "J2") (pin "07") (pinfunction "~WAIT_07") (pintype "input"))
    )
  )
)
